# ReliefBoard.net
KiCad netlist of a schematic drawn in EAGLE
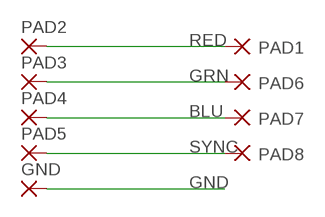
[diagram p0: schematic, sheet 1]

(export (version "E")
  (design (tool "Eeschema 10.0.6"))
  (components
    (comp (ref "GND")
      (value "SMD2")
      (footprint "eagle-import:SMD1,27-2,54")
      (libsource (lib "eagle-import") (part "SMD2"))
    )
    (comp (ref "PAD1")
      (value "SMD2")
      (footprint "eagle-import:SMD1,27-2,54")
      (libsource (lib "eagle-import") (part "SMD2"))
    )
    (comp (ref "PAD2")
      (value "SMD2")
      (footprint "eagle-import:SMD1,27-2,54")
      (libsource (lib "eagle-import") (part "SMD2"))
    )
    (comp (ref "PAD3")
      (value "SMD2")
      (footprint "eagle-import:SMD1,27-2,54")
      (libsource (lib "eagle-import") (part "SMD2"))
    )
    (comp (ref "PAD4")
      (value "SMD2")
      (footprint "eagle-import:SMD1,27-2,54")
      (libsource (lib "eagle-import") (part "SMD2"))
    )
    (comp (ref "PAD5")
      (value "SMD2")
      (footprint "eagle-import:SMD1,27-2,54")
      (libsource (lib "eagle-import") (part "SMD2"))
    )
    (comp (ref "PAD6")
      (value "SMD2")
      (footprint "eagle-import:SMD1,27-2,54")
      (libsource (lib "eagle-import") (part "SMD2"))
    )
    (comp (ref "PAD7")
      (value "SMD2")
      (footprint "eagle-import:SMD1,27-2,54")
      (libsource (lib "eagle-import") (part "SMD2"))
    )
    (comp (ref "PAD8")
      (value "SMD2")
      (footprint "eagle-import:SMD1,27-2,54")
      (libsource (lib "eagle-import") (part "SMD2"))
    )
  )
  (nets
    (net (code "1") (name "/BLU") (class "Default")
      (node (ref "PAD4") (pin "1") (pinfunction "P_1") (pintype "passive"))
      (node (ref "PAD7") (pin "1") (pinfunction "P_1") (pintype "passive"))
    )
    (net (code "2") (name "/GND") (class "Default")
      (node (ref "GND") (pin "1") (pinfunction "P_1") (pintype "passive"))
    )
    (net (code "3") (name "/GRN") (class "Default")
      (node (ref "PAD3") (pin "1") (pinfunction "P_1") (pintype "passive"))
      (node (ref "PAD6") (pin "1") (pinfunction "P_1") (pintype "passive"))
    )
    (net (code "4") (name "/RED") (class "Default")
      (node (ref "PAD1") (pin "1") (pinfunction "P_1") (pintype "passive"))
      (node (ref "PAD2") (pin "1") (pinfunction "P_1") (pintype "passive"))
    )
    (net (code "5") (name "/SYNC") (class "Default")
      (node (ref "PAD5") (pin "1") (pinfunction "P_1") (pintype "passive"))
      (node (ref "PAD8") (pin "1") (pinfunction "P_1") (pintype "passive"))
    )
  )
)
